# Main.net
KiCad netlist of a schematic drawn in Altium Designer
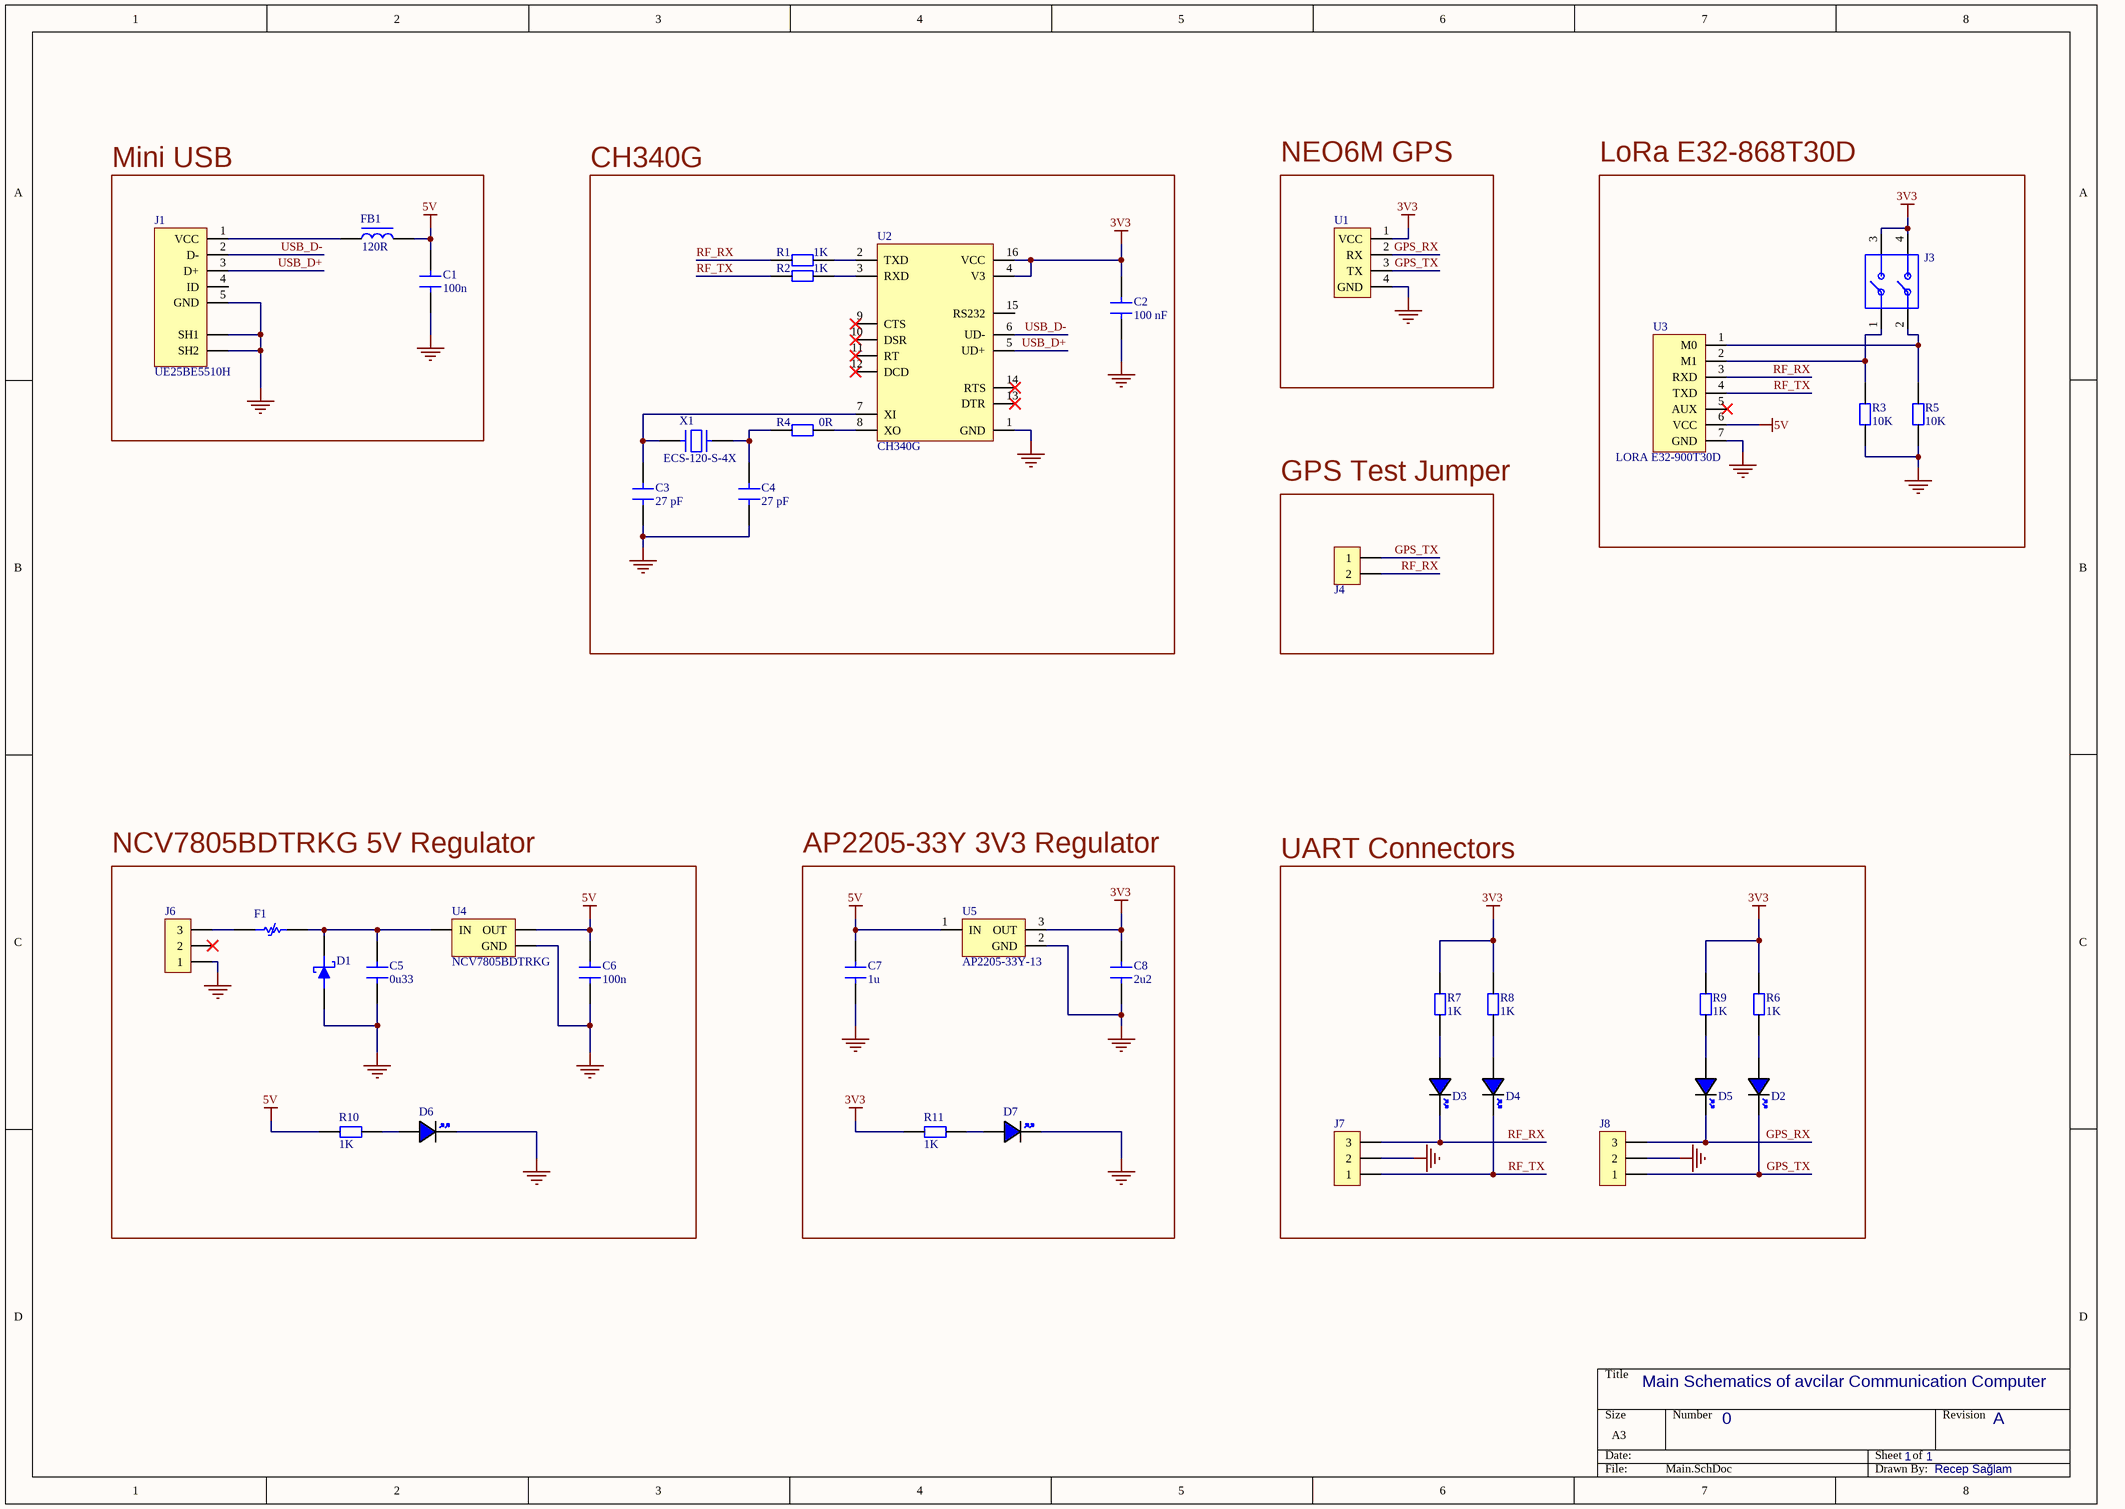
[diagram p0: Main.SchDoc]

(export (version "E")
  (design (tool "Eeschema 10.0.6"))
  (components
    (comp (ref "C1")
      (value "100n")
      (footprint "CAP 0805")
      (description "Capacitor SMD 0805 50V")
      (libsource (lib "Schlib") (part "CAP 0805 50V"))
    )
    (comp (ref "C2")
      (value "100 nF")
      (footprint "CAP 0805")
      (description "Capacitor SMD 0805 50V")
      (libsource (lib "Schlib") (part "CAP 0805 50V"))
    )
    (comp (ref "C3")
      (value "27 pF")
      (footprint "CAP 0603")
      (description "Capacitor SMD 0603 50V")
      (libsource (lib "Schlib") (part "CAP 0603 50V"))
    )
    (comp (ref "C4")
      (value "27 pF")
      (footprint "CAP 0603")
      (description "Capacitor SMD 0603 50V")
      (libsource (lib "Schlib") (part "CAP 0603 50V"))
    )
    (comp (ref "C5")
      (value "0u33")
      (footprint "CAP 0805")
      (description "Capacitor SMD 0805 50V")
      (libsource (lib "Schlib") (part "CAP 0805 50V"))
    )
    (comp (ref "C6")
      (value "100n")
      (footprint "CAP 0805")
      (description "Capacitor SMD 0805 50V")
      (libsource (lib "Schlib") (part "CAP 0805 50V"))
    )
    (comp (ref "C7")
      (value "1u")
      (footprint "CAP 0805")
      (description "Capacitor SMD 0805 50V")
      (libsource (lib "Schlib") (part "CAP 0805 50V"))
    )
    (comp (ref "C8")
      (value "2u2")
      (footprint "CAP 0805")
      (description "Capacitor SMD 0805 50V")
      (libsource (lib "Schlib") (part "CAP 0805 50V"))
    )
    (comp (ref "D1")
      (value "SMBJ8.0CA-13-F")
      (footprint "SMBJ12CA-13-F")
      (description "SMBJ Series 8 V 600 W SMT Bi-Directional Transient Voltage Suppressor - SMB")
      (fields (field (name "MANUFACTURER") "Diodes Zetex"))
      (libsource (lib "Schlib") (part "SMBJ8.0CA-13-F"))
    )
    (comp (ref "D2")
      (value "LED 0805 BLUE")
      (footprint "LED 0805 BLUE")
      (description "LED 0805 GREEN SMD")
      (libsource (lib "Schlib") (part "LED 0805 BLUE"))
    )
    (comp (ref "D3")
      (value "LED 0805 BLUE")
      (footprint "LED 0805 BLUE")
      (description "LED 0805 GREEN SMD")
      (libsource (lib "Schlib") (part "LED 0805 BLUE"))
    )
    (comp (ref "D4")
      (value "LED 0805 BLUE")
      (footprint "LED 0805 BLUE")
      (description "LED 0805 GREEN SMD")
      (libsource (lib "Schlib") (part "LED 0805 BLUE"))
    )
    (comp (ref "D5")
      (value "LED 0805 BLUE")
      (footprint "LED 0805 BLUE")
      (description "LED 0805 GREEN SMD")
      (libsource (lib "Schlib") (part "LED 0805 BLUE"))
    )
    (comp (ref "D6")
      (value "LED 0805 BLUE")
      (footprint "LED 0805 BLUE")
      (description "LED 0805 GREEN SMD")
      (libsource (lib "Schlib") (part "LED 0805 BLUE"))
    )
    (comp (ref "D7")
      (value "LED 0805 BLUE")
      (footprint "LED 0805 BLUE")
      (description "LED 0805 GREEN SMD")
      (libsource (lib "Schlib") (part "LED 0805 BLUE"))
    )
    (comp (ref "F1")
      (value "0ZCG0075FF2C")
      (footprint "0ZCG0075FF2C")
      (fields (field (name "MANUFACTURER") "Bel"))
      (libsource (lib "Schlib") (part "0ZCG0075FF2C"))
    )
    (comp (ref "FB1")
      (value "120R")
      (footprint "FB 0805")
      (description "Ferrite Bead SMD 0805")
      (libsource (lib "Schlib") (part "FB 0805"))
    )
    (comp (ref "J1")
      (value "UE25BE5510H")
      (footprint "UE25BE55H")
      (description "Conn Mini USB 2.0 Type B RCP 5 POS 0.8mm Solder ST Thru-Hole 5 Terminal 1 Port")
      (fields (field (name "MANUFACTURER") "Amphenol Commercial"))
      (libsource (lib "Schlib") (part "UE25BE5510H"))
    )
    (comp (ref "J3")
      (value "2 Pin DIP Switch")
      (footprint "2 PIN DIP SWITCH")
      (libsource (lib "Schlib") (part "2 Pin DIP Switch"))
    )
    (comp (ref "J4")
      (value "1x2 HEADER MALE")
      (footprint "1x2 HEADER MALE")
      (libsource (lib "Schlib") (part "1x2 HEADER MALE"))
    )
    (comp (ref "J6")
      (value "JST B3B-XH-A")
      (footprint "JST_B3B-XH-A")
      (description "Connector Header, XH Series, 3 Position, 2.50mm, Through Hole, Press-Fit, Solder, Natural")
      (fields
        (field (name "MANUFACTURER") "JST")
        (field (name "MANUFACTURER PART NUMBER") "B3B-XH-A(LF)(SN)")
      )
      (libsource (lib "Schlib") (part "JST B3B-XH-A"))
    )
    (comp (ref "J7")
      (value "JST B3B-XH-A")
      (footprint "JST_B3B-XH-A")
      (description "Connector Header, XH Series, 3 Position, 2.50mm, Through Hole, Press-Fit, Solder, Natural")
      (fields
        (field (name "MANUFACTURER") "JST")
        (field (name "MANUFACTURER PART NUMBER") "B3B-XH-A(LF)(SN)")
      )
      (libsource (lib "Schlib") (part "JST B3B-XH-A"))
    )
    (comp (ref "J8")
      (value "JST B3B-XH-A")
      (footprint "JST_B3B-XH-A")
      (description "Connector Header, XH Series, 3 Position, 2.50mm, Through Hole, Press-Fit, Solder, Natural")
      (fields
        (field (name "MANUFACTURER") "JST")
        (field (name "MANUFACTURER PART NUMBER") "B3B-XH-A(LF)(SN)")
      )
      (libsource (lib "Schlib") (part "JST B3B-XH-A"))
    )
    (comp (ref "R1")
      (value "1K")
      (footprint "RES 0805")
      (description "Resistor SMD 0805")
      (libsource (lib "Schlib") (part "RES 0805"))
    )
    (comp (ref "R2")
      (value "1K")
      (footprint "RES 0805")
      (description "Resistor SMD 0805")
      (libsource (lib "Schlib") (part "RES 0805"))
    )
    (comp (ref "R3")
      (value "10K")
      (footprint "RES 0805")
      (description "Resistor SMD 0805")
      (libsource (lib "Schlib") (part "RES 0805"))
    )
    (comp (ref "R4")
      (value "0R")
      (footprint "RES 0603")
      (description "Resistor SMD 0603")
      (libsource (lib "Schlib") (part "RES 0603"))
    )
    (comp (ref "R5")
      (value "10K")
      (footprint "RES 0805")
      (description "Resistor SMD 0805")
      (libsource (lib "Schlib") (part "RES 0805"))
    )
    (comp (ref "R6")
      (value "1K")
      (footprint "RES 0805")
      (description "Resistor SMD 0805")
      (libsource (lib "Schlib") (part "RES 0805"))
    )
    (comp (ref "R7")
      (value "1K")
      (footprint "RES 0805")
      (description "Resistor SMD 0805")
      (libsource (lib "Schlib") (part "RES 0805"))
    )
    (comp (ref "R8")
      (value "1K")
      (footprint "RES 0805")
      (description "Resistor SMD 0805")
      (libsource (lib "Schlib") (part "RES 0805"))
    )
    (comp (ref "R9")
      (value "1K")
      (footprint "RES 0805")
      (description "Resistor SMD 0805")
      (libsource (lib "Schlib") (part "RES 0805"))
    )
    (comp (ref "R10")
      (value "1K")
      (footprint "RES 0805")
      (description "Resistor SMD 0805")
      (libsource (lib "Schlib") (part "RES 0805"))
    )
    (comp (ref "R11")
      (value "1K")
      (footprint "RES 0805")
      (description "Resistor SMD 0805")
      (libsource (lib "Schlib") (part "RES 0805"))
    )
    (comp (ref "U1")
      (value "GPS GY-NEO6MV2")
      (footprint "GPS GY-NEO6MV2")
      (description "GY-NEO6MV2 GPS Module")
      (libsource (lib "Schlib") (part "GPS GY-NEO6MV2"))
    )
    (comp (ref "U2")
      (value "CH340G")
      (footprint "CH340G")
      (description "USB Interface Integrated Circuit")
      (libsource (lib "Schlib") (part "CH340G"))
    )
    (comp (ref "U3")
      (value "LORA E32-900T30D")
      (footprint "LORA E32-900T30D")
      (description "SX1276 E32-868T30D LoRa Module")
      (libsource (lib "Schlib") (part "LORA E32-900T30D"))
    )
    (comp (ref "U4")
      (value "NCV7805BDTRKG")
      (footprint "L78M05CDT-TR")
      (description "IC REG LDO 5V 0.5A DPAK")
      (fields
        (field (name "MANUFACTURER") "STMicroelectronics")
        (field (name "MANUFACTURER PART NUMBER") "L78M05CDT-TR")
      )
      (libsource (lib "Schlib") (part "L78M05CDT-TR"))
    )
    (comp (ref "U5")
      (value "AP2205-33Y-13")
      (footprint "AP2205-33Y-13")
      (description "Ldo, Fixed, 3.3V, 0.2A, Sot-89-3 Rohs Compliant: Yes ¦Diodes Inc. AP2205-33Y-13")
      (fields (field (name "MANUFACTURER") "Diodes"))
      (libsource (lib "Schlib") (part "AP2205-33Y-13"))
    )
    (comp (ref "X1")
      (value "ECS-120-S-4X")
      (footprint "XTAL_ECS-120-S-4X")
      (description "Crystal 12MHz ±30ppm (Tol) ±50ppm (Stability) Series FUND 60Ohm 2-Pin HC-49/USX Thru-Hole Bulk")
      (fields (field (name "MANUFACTURER") "ECS International") (field (name "TOLERANCE") "30ppm"))
      (libsource (lib "Schlib") (part "ECS-120-S-4X"))
    )
  )
  (nets
    (net (code "1") (name "/GPS_RX") (class "Default")
      (node (ref "D5") (pin "K") (pinfunction "K_K") (pintype "passive"))
      (node (ref "J8") (pin "3") (pinfunction "3_3") (pintype "passive"))
      (node (ref "U1") (pin "2") (pinfunction "RX_2") (pintype "passive"))
    )
    (net (code "2") (name "/GPS_TX") (class "Default")
      (node (ref "D2") (pin "K") (pinfunction "K_K") (pintype "passive"))
      (node (ref "J4") (pin "1") (pinfunction "1_1") (pintype "passive"))
      (node (ref "J8") (pin "1") (pinfunction "1_1") (pintype "passive"))
      (node (ref "U1") (pin "3") (pinfunction "TX_3") (pintype "passive"))
    )
    (net (code "3") (name "/RF_RX") (class "Default")
      (node (ref "D3") (pin "K") (pinfunction "K_K") (pintype "passive"))
      (node (ref "J4") (pin "2") (pinfunction "2_2") (pintype "passive"))
      (node (ref "J7") (pin "3") (pinfunction "3_3") (pintype "passive"))
      (node (ref "R1") (pin "1") (pinfunction "1_1") (pintype "passive"))
      (node (ref "U3") (pin "3") (pinfunction "RXD_3") (pintype "passive"))
    )
    (net (code "4") (name "/RF_TX") (class "Default")
      (node (ref "D4") (pin "K") (pinfunction "K_K") (pintype "passive"))
      (node (ref "J7") (pin "1") (pinfunction "1_1") (pintype "passive"))
      (node (ref "R2") (pin "1") (pinfunction "1_1") (pintype "passive"))
      (node (ref "U3") (pin "4") (pinfunction "TXD_4") (pintype "passive"))
    )
    (net (code "5") (name "/USB_D+") (class "Default")
      (node (ref "J1") (pin "3") (pinfunction "D+_3") (pintype "passive"))
      (node (ref "U2") (pin "5") (pinfunction "UD+_5") (pintype "passive"))
    )
    (net (code "6") (name "/USB_D-") (class "Default")
      (node (ref "J1") (pin "2") (pinfunction "D-_2") (pintype "passive"))
      (node (ref "U2") (pin "6") (pinfunction "UD-_6") (pintype "passive"))
    )
    (net (code "7") (name "3V3") (class "Default")
      (node (ref "C2") (pin "2") (pinfunction "2_2") (pintype "passive"))
      (node (ref "C8") (pin "2") (pinfunction "2_2") (pintype "passive"))
      (node (ref "J3") (pin "3") (pinfunction "3_3") (pintype "passive"))
      (node (ref "J3") (pin "4") (pinfunction "4_4") (pintype "passive"))
      (node (ref "R11") (pin "1") (pinfunction "1_1") (pintype "passive"))
      (node (ref "R6") (pin "1") (pinfunction "1_1") (pintype "passive"))
      (node (ref "R7") (pin "1") (pinfunction "1_1") (pintype "passive"))
      (node (ref "R8") (pin "1") (pinfunction "1_1") (pintype "passive"))
      (node (ref "R9") (pin "1") (pinfunction "1_1") (pintype "passive"))
      (node (ref "U1") (pin "1") (pinfunction "VCC_1") (pintype "passive"))
      (node (ref "U2") (pin "16") (pinfunction "VCC_16") (pintype "passive"))
      (node (ref "U2") (pin "4") (pinfunction "V3_4") (pintype "passive"))
      (node (ref "U5") (pin "3") (pinfunction "OUT_3") (pintype "passive"))
    )
    (net (code "8") (name "5V") (class "Default")
      (node (ref "C1") (pin "2") (pinfunction "2_2") (pintype "passive"))
      (node (ref "C6") (pin "2") (pinfunction "2_2") (pintype "passive"))
      (node (ref "C7") (pin "2") (pinfunction "2_2") (pintype "passive"))
      (node (ref "FB1") (pin "2") (pintype "passive"))
      (node (ref "R10") (pin "1") (pinfunction "1_1") (pintype "passive"))
      (node (ref "U3") (pin "6") (pinfunction "VCC_6") (pintype "passive"))
      (node (ref "U4") (pin "3") (pinfunction "OUT_3") (pintype "passive"))
      (node (ref "U5") (pin "1") (pinfunction "IN_1") (pintype "passive"))
    )
    (net (code "9") (name "GND") (class "Default")
      (node (ref "C1") (pin "1") (pinfunction "1_1") (pintype "passive"))
      (node (ref "C2") (pin "1") (pinfunction "1_1") (pintype "passive"))
      (node (ref "C3") (pin "1") (pinfunction "1_1") (pintype "passive"))
      (node (ref "C4") (pin "1") (pinfunction "1_1") (pintype "passive"))
      (node (ref "C5") (pin "1") (pinfunction "1_1") (pintype "passive"))
      (node (ref "C6") (pin "1") (pinfunction "1_1") (pintype "passive"))
      (node (ref "C7") (pin "1") (pinfunction "1_1") (pintype "passive"))
      (node (ref "C8") (pin "1") (pinfunction "1_1") (pintype "passive"))
      (node (ref "D1") (pin "1") (pintype "passive"))
      (node (ref "D6") (pin "K") (pinfunction "K_K") (pintype "passive"))
      (node (ref "D7") (pin "K") (pinfunction "K_K") (pintype "passive"))
      (node (ref "J1") (pin "5") (pinfunction "GND_5") (pintype "passive"))
      (node (ref "J1") (pin "SH1") (pinfunction "SH1_SH1") (pintype "passive"))
      (node (ref "J1") (pin "SH2") (pinfunction "SH2_SH2") (pintype "passive"))
      (node (ref "J6") (pin "1") (pinfunction "1_1") (pintype "passive"))
      (node (ref "J7") (pin "2") (pinfunction "2_2") (pintype "passive"))
      (node (ref "J8") (pin "2") (pinfunction "2_2") (pintype "passive"))
      (node (ref "R3") (pin "1") (pinfunction "1_1") (pintype "passive"))
      (node (ref "R5") (pin "1") (pinfunction "1_1") (pintype "passive"))
      (node (ref "U1") (pin "4") (pinfunction "GND_4") (pintype "passive"))
      (node (ref "U2") (pin "1") (pinfunction "GND_1") (pintype "passive"))
      (node (ref "U3") (pin "7") (pinfunction "GND_7") (pintype "passive"))
      (node (ref "U4") (pin "2") (pinfunction "GND_2") (pintype "passive"))
      (node (ref "U5") (pin "2") (pinfunction "GND_2") (pintype "passive"))
    )
    (net (code "10") (name "Net-(C4-Pad2)") (class "Default")
      (node (ref "C4") (pin "2") (pinfunction "2_2") (pintype "passive"))
      (node (ref "R4") (pin "1") (pinfunction "1_1") (pintype "passive"))
      (node (ref "X1") (pin "2") (pinfunction "2_2") (pintype "passive"))
    )
    (net (code "11") (name "Net-(D2-PadA)") (class "Default")
      (node (ref "D2") (pin "A") (pinfunction "A_A") (pintype "passive"))
      (node (ref "R6") (pin "2") (pinfunction "2_2") (pintype "passive"))
    )
    (net (code "12") (name "Net-(D3-PadA)") (class "Default")
      (node (ref "D3") (pin "A") (pinfunction "A_A") (pintype "passive"))
      (node (ref "R7") (pin "2") (pinfunction "2_2") (pintype "passive"))
    )
    (net (code "13") (name "Net-(D4-PadA)") (class "Default")
      (node (ref "D4") (pin "A") (pinfunction "A_A") (pintype "passive"))
      (node (ref "R8") (pin "2") (pinfunction "2_2") (pintype "passive"))
    )
    (net (code "14") (name "Net-(D5-PadA)") (class "Default")
      (node (ref "D5") (pin "A") (pinfunction "A_A") (pintype "passive"))
      (node (ref "R9") (pin "2") (pinfunction "2_2") (pintype "passive"))
    )
    (net (code "15") (name "Net-(D6-PadA)") (class "Default")
      (node (ref "D6") (pin "A") (pinfunction "A_A") (pintype "passive"))
      (node (ref "R10") (pin "2") (pinfunction "2_2") (pintype "passive"))
    )
    (net (code "16") (name "Net-(D7-PadA)") (class "Default")
      (node (ref "D7") (pin "A") (pinfunction "A_A") (pintype "passive"))
      (node (ref "R11") (pin "2") (pinfunction "2_2") (pintype "passive"))
    )
    (net (code "17") (name "Net-(F1-Pad1)") (class "Default")
      (node (ref "F1") (pin "1") (pintype "passive"))
      (node (ref "J6") (pin "3") (pinfunction "3_3") (pintype "passive"))
    )
    (net (code "18") (name "Net-(J1-VCC)") (class "Default")
      (node (ref "FB1") (pin "1") (pintype "passive"))
      (node (ref "J1") (pin "1") (pinfunction "VCC_1") (pintype "passive"))
    )
    (net (code "19") (name "Net-(U2-RXD)") (class "Default")
      (node (ref "R2") (pin "2") (pinfunction "2_2") (pintype "passive"))
      (node (ref "U2") (pin "3") (pinfunction "RXD_3") (pintype "passive"))
    )
    (net (code "20") (name "Net-(U2-TXD)") (class "Default")
      (node (ref "R1") (pin "2") (pinfunction "2_2") (pintype "passive"))
      (node (ref "U2") (pin "2") (pinfunction "TXD_2") (pintype "passive"))
    )
    (net (code "21") (name "Net-(U2-XI)") (class "Default")
      (node (ref "C3") (pin "2") (pinfunction "2_2") (pintype "passive"))
      (node (ref "U2") (pin "7") (pinfunction "XI_7") (pintype "passive"))
      (node (ref "X1") (pin "1") (pinfunction "1_1") (pintype "passive"))
    )
    (net (code "22") (name "Net-(U2-XO)") (class "Default")
      (node (ref "R4") (pin "2") (pinfunction "2_2") (pintype "passive"))
      (node (ref "U2") (pin "8") (pinfunction "XO_8") (pintype "passive"))
    )
    (net (code "23") (name "Net-(U3-M0)") (class "Default")
      (node (ref "J3") (pin "2") (pinfunction "2_2") (pintype "passive"))
      (node (ref "R5") (pin "2") (pinfunction "2_2") (pintype "passive"))
      (node (ref "U3") (pin "1") (pinfunction "M0_1") (pintype "passive"))
    )
    (net (code "24") (name "Net-(U3-M1)") (class "Default")
      (node (ref "J3") (pin "1") (pinfunction "1_1") (pintype "passive"))
      (node (ref "R3") (pin "2") (pinfunction "2_2") (pintype "passive"))
      (node (ref "U3") (pin "2") (pinfunction "M1_2") (pintype "passive"))
    )
    (net (code "25") (name "Net-(U4-IN)") (class "Default")
      (node (ref "C5") (pin "2") (pinfunction "2_2") (pintype "passive"))
      (node (ref "D1") (pin "2") (pintype "passive"))
      (node (ref "F1") (pin "2") (pintype "passive"))
      (node (ref "U4") (pin "1") (pinfunction "IN_1") (pintype "passive"))
    )
    (net (code "26") (name "unconnected-(J1-ID-Pad4)") (class "Default")
      (node (ref "J1") (pin "4") (pinfunction "ID_4") (pintype "passive"))
    )
    (net (code "27") (name "unconnected-(J6-Pad2)") (class "Default")
      (node (ref "J6") (pin "2") (pinfunction "2_2") (pintype "passive+no_connect"))
    )
    (net (code "28") (name "unconnected-(U2-CTS-Pad9)") (class "Default")
      (node (ref "U2") (pin "9") (pinfunction "CTS_9") (pintype "passive+no_connect"))
    )
    (net (code "29") (name "unconnected-(U2-DCD-Pad12)") (class "Default")
      (node (ref "U2") (pin "12") (pinfunction "DCD_12") (pintype "passive+no_connect"))
    )
    (net (code "30") (name "unconnected-(U2-DSR-Pad10)") (class "Default")
      (node (ref "U2") (pin "10") (pinfunction "DSR_10") (pintype "passive+no_connect"))
    )
    (net (code "31") (name "unconnected-(U2-DTR-Pad13)") (class "Default")
      (node (ref "U2") (pin "13") (pinfunction "DTR_13") (pintype "passive+no_connect"))
    )
    (net (code "32") (name "unconnected-(U2-RS232-Pad15)") (class "Default")
      (node (ref "U2") (pin "15") (pinfunction "RS232_15") (pintype "passive"))
    )
    (net (code "33") (name "unconnected-(U2-RT-Pad11)") (class "Default")
      (node (ref "U2") (pin "11") (pinfunction "RT_11") (pintype "passive+no_connect"))
    )
    (net (code "34") (name "unconnected-(U2-RTS-Pad14)") (class "Default")
      (node (ref "U2") (pin "14") (pinfunction "RTS_14") (pintype "passive+no_connect"))
    )
    (net (code "35") (name "unconnected-(U3-AUX-Pad5)") (class "Default")
      (node (ref "U3") (pin "5") (pinfunction "AUX_5") (pintype "passive+no_connect"))
    )
  )
)
